# 08_ADC_measure.net
KiCad netlist of a schematic drawn in Altium Designer
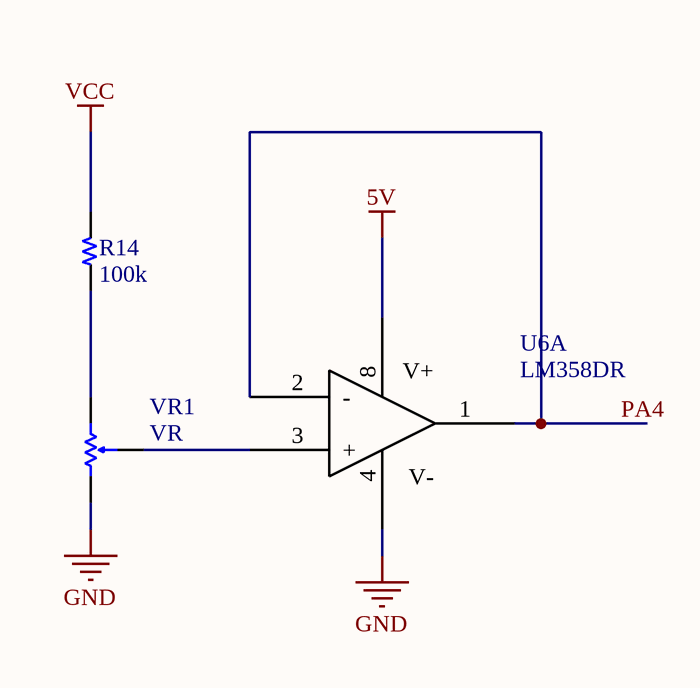
[diagram p0: 08_ADC_measure.SchDoc]

(export (version "E")
  (design (tool "Eeschema 10.0.6"))
  (components
    (comp (ref "R14")
      (value "100k")
      (footprint "R 0805")
      (description "Resistor")
      (libsource (lib "chipfc_libs") (part "Resistor"))
    )
    (comp (ref "U6")
      (value "LM358DR")
      (footprint "LM358DR")
      (description "Operational Amplifiers - Op Amps Dual Op Amp")
      (fields (field (name "MANUFACTURER") "Texas Instruments") (field (name "LCSC PART #") "C5423"))
      (libsource (lib "OPAMP") (part "LM358DR"))
    )
    (comp (ref "VR1")
      (value "VR")
      (footprint "R VAR E")
      (description "Resistor Variable")
      (libsource (lib "chipfc_libs") (part "Resistor Variable"))
    )
  )
  (nets
    (net (code "1") (name "/PA4") (class "Default")
      (node (ref "U6") (pin "1") (pinfunction "OUT_1_1") (pintype "passive"))
      (node (ref "U6") (pin "2") (pinfunction "-_2") (pintype "passive"))
    )
    (net (code "2") (name "5V") (class "Default")
      (node (ref "U6") (pin "8") (pinfunction "VCC_8") (pintype "passive"))
    )
    (net (code "3") (name "GND") (class "Default")
      (node (ref "U6") (pin "4") (pinfunction "GND_4") (pintype "passive"))
      (node (ref "VR1") (pin "3") (pinfunction "3_3") (pintype "passive"))
    )
    (net (code "4") (name "Net-(R14-Pad1)") (class "Default")
      (node (ref "R14") (pin "1") (pinfunction "1_1") (pintype "passive"))
      (node (ref "VR1") (pin "1") (pinfunction "1_1") (pintype "passive"))
    )
    (net (code "5") (name "Net-(U6A-+)") (class "Default")
      (node (ref "U6") (pin "3") (pinfunction "+_3") (pintype "passive"))
      (node (ref "VR1") (pin "2") (pinfunction "2_2") (pintype "passive"))
    )
    (net (code "6") (name "VCC") (class "Default")
      (node (ref "R14") (pin "2") (pinfunction "2_2") (pintype "passive"))
    )
  )
)
